# connector2.net
KiCad netlist of a schematic drawn in EAGLE
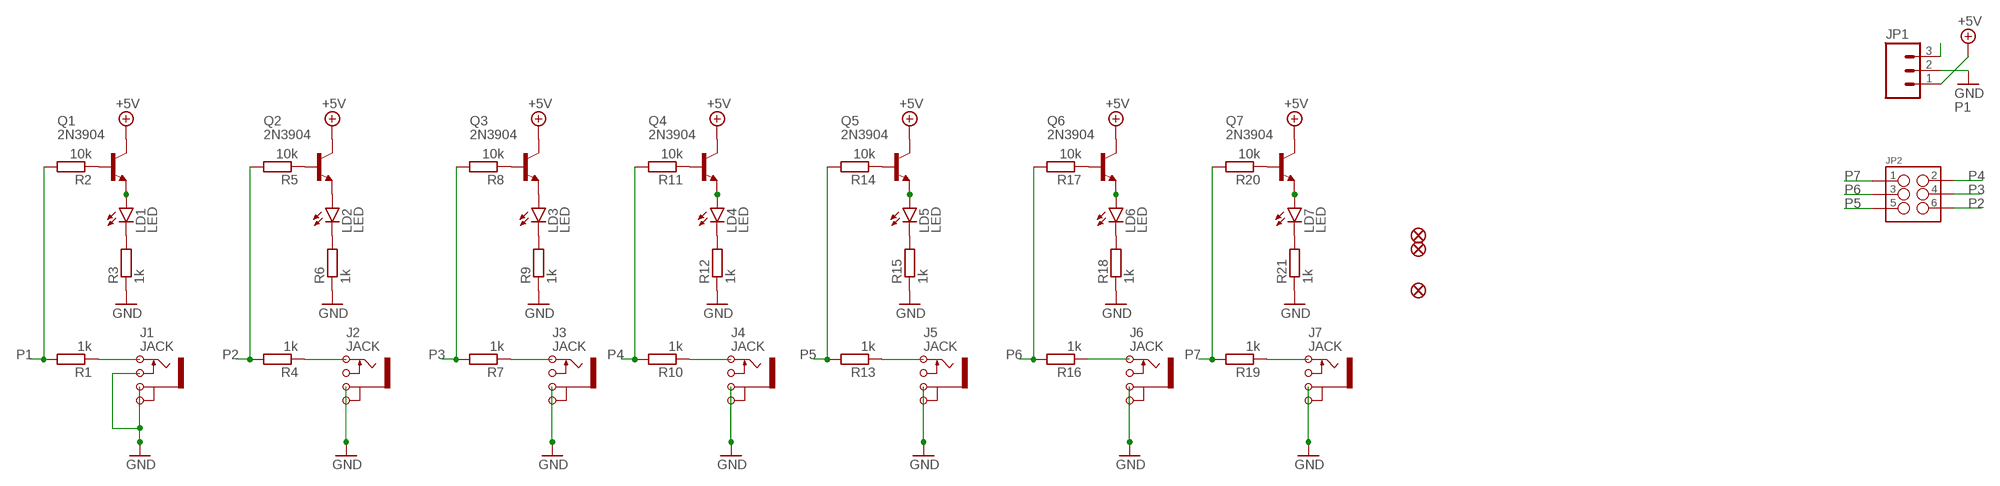
[diagram p0: schematic, sheet 1]

(export (version "E")
  (design (tool "Eeschema 10.0.6"))
  (components
    (comp (ref "FID1")
      (value "FIDUCIAL")
      (footprint "eagle-import:FIDUCIAL")
      (libsource (lib "eagle-import") (part "FIDUCIAL"))
    )
    (comp (ref "FID2")
      (value "FIDUCIAL")
      (footprint "eagle-import:FIDUCIAL")
      (libsource (lib "eagle-import") (part "FIDUCIAL"))
    )
    (comp (ref "FID3")
      (value "FIDUCIAL")
      (footprint "eagle-import:FIDUCIAL")
      (libsource (lib "eagle-import") (part "FIDUCIAL"))
    )
    (comp (ref "J1")
      (value "JACK")
      (footprint "eagle-import:JACK_MONO")
      (libsource (lib "eagle-import") (part "JACK_MONOJACK_MONO"))
    )
    (comp (ref "J2")
      (value "JACK")
      (footprint "eagle-import:JACK_MONO")
      (libsource (lib "eagle-import") (part "JACK_MONOJACK_MONO"))
    )
    (comp (ref "J3")
      (value "JACK")
      (footprint "eagle-import:JACK_MONO")
      (libsource (lib "eagle-import") (part "JACK_MONOJACK_MONO"))
    )
    (comp (ref "J4")
      (value "JACK")
      (footprint "eagle-import:JACK_MONO")
      (libsource (lib "eagle-import") (part "JACK_MONOJACK_MONO"))
    )
    (comp (ref "J5")
      (value "JACK")
      (footprint "eagle-import:JACK_MONO")
      (libsource (lib "eagle-import") (part "JACK_MONOJACK_MONO"))
    )
    (comp (ref "J6")
      (value "JACK")
      (footprint "eagle-import:JACK_MONO")
      (libsource (lib "eagle-import") (part "JACK_MONOJACK_MONO"))
    )
    (comp (ref "J7")
      (value "JACK")
      (footprint "eagle-import:JACK_MONO")
      (libsource (lib "eagle-import") (part "JACK_MONOJACK_MONO"))
    )
    (comp (ref "JP1")
      (value "M03LOCK")
      (footprint "eagle-import:1X03_LOCK")
      (libsource (lib "eagle-import") (part "M03LOCK"))
    )
    (comp (ref "JP2")
      (value "M03X2NO_SILK")
      (footprint "eagle-import:2X3-NS")
      (libsource (lib "eagle-import") (part "M03X2NO_SILK"))
    )
    (comp (ref "LD1")
      (value "LED")
      (footprint "eagle-import:LEDSMALLHOLES")
      (libsource (lib "eagle-import") (part "LED_THT"))
    )
    (comp (ref "LD2")
      (value "LED")
      (footprint "eagle-import:LEDSMALLHOLES")
      (libsource (lib "eagle-import") (part "LED_THT"))
    )
    (comp (ref "LD3")
      (value "LED")
      (footprint "eagle-import:LEDSMALLHOLES")
      (libsource (lib "eagle-import") (part "LED_THT"))
    )
    (comp (ref "LD4")
      (value "LED")
      (footprint "eagle-import:LEDSMALLHOLES")
      (libsource (lib "eagle-import") (part "LED_THT"))
    )
    (comp (ref "LD5")
      (value "LED")
      (footprint "eagle-import:LEDSMALLHOLES")
      (libsource (lib "eagle-import") (part "LED_THT"))
    )
    (comp (ref "LD6")
      (value "LED")
      (footprint "eagle-import:LEDSMALLHOLES")
      (libsource (lib "eagle-import") (part "LED_THT"))
    )
    (comp (ref "LD7")
      (value "LED")
      (footprint "eagle-import:LEDSMALLHOLES")
      (libsource (lib "eagle-import") (part "LED_THT"))
    )
    (comp (ref "Q1")
      (value "2N3904")
      (footprint "eagle-import:SOT23")
      (fields (field (name "MPN") "MMBT3904LT1G"))
      (libsource (lib "eagle-import") (part "2N3904"))
    )
    (comp (ref "Q2")
      (value "2N3904")
      (footprint "eagle-import:SOT23")
      (fields (field (name "MPN") "MMBT3904LT1G"))
      (libsource (lib "eagle-import") (part "2N3904"))
    )
    (comp (ref "Q3")
      (value "2N3904")
      (footprint "eagle-import:SOT23")
      (fields (field (name "MPN") "MMBT3904LT1G"))
      (libsource (lib "eagle-import") (part "2N3904"))
    )
    (comp (ref "Q4")
      (value "2N3904")
      (footprint "eagle-import:SOT23")
      (fields (field (name "MPN") "MMBT3904LT1G"))
      (libsource (lib "eagle-import") (part "2N3904"))
    )
    (comp (ref "Q5")
      (value "2N3904")
      (footprint "eagle-import:SOT23")
      (fields (field (name "MPN") "MMBT3904LT1G"))
      (libsource (lib "eagle-import") (part "2N3904"))
    )
    (comp (ref "Q6")
      (value "2N3904")
      (footprint "eagle-import:SOT23")
      (fields (field (name "MPN") "MMBT3904LT1G"))
      (libsource (lib "eagle-import") (part "2N3904"))
    )
    (comp (ref "Q7")
      (value "2N3904")
      (footprint "eagle-import:SOT23")
      (fields (field (name "MPN") "MMBT3904LT1G"))
      (libsource (lib "eagle-import") (part "2N3904"))
    )
    (comp (ref "R1")
      (value "1k")
      (footprint "eagle-import:RESISTOR0603")
      (libsource (lib "eagle-import") (part "RESISTOR0603"))
    )
    (comp (ref "R2")
      (value "10k")
      (footprint "eagle-import:RESISTOR0603")
      (libsource (lib "eagle-import") (part "RESISTOR0603"))
    )
    (comp (ref "R3")
      (value "1k")
      (footprint "eagle-import:RESISTOR0603")
      (libsource (lib "eagle-import") (part "RESISTOR0603"))
    )
    (comp (ref "R4")
      (value "1k")
      (footprint "eagle-import:RESISTOR0603")
      (libsource (lib "eagle-import") (part "RESISTOR0603"))
    )
    (comp (ref "R5")
      (value "10k")
      (footprint "eagle-import:RESISTOR0603")
      (libsource (lib "eagle-import") (part "RESISTOR0603"))
    )
    (comp (ref "R6")
      (value "1k")
      (footprint "eagle-import:RESISTOR0603")
      (libsource (lib "eagle-import") (part "RESISTOR0603"))
    )
    (comp (ref "R7")
      (value "1k")
      (footprint "eagle-import:RESISTOR0603")
      (libsource (lib "eagle-import") (part "RESISTOR0603"))
    )
    (comp (ref "R8")
      (value "10k")
      (footprint "eagle-import:RESISTOR0603")
      (libsource (lib "eagle-import") (part "RESISTOR0603"))
    )
    (comp (ref "R9")
      (value "1k")
      (footprint "eagle-import:RESISTOR0603")
      (libsource (lib "eagle-import") (part "RESISTOR0603"))
    )
    (comp (ref "R10")
      (value "1k")
      (footprint "eagle-import:RESISTOR0603")
      (libsource (lib "eagle-import") (part "RESISTOR0603"))
    )
    (comp (ref "R11")
      (value "10k")
      (footprint "eagle-import:RESISTOR0603")
      (libsource (lib "eagle-import") (part "RESISTOR0603"))
    )
    (comp (ref "R12")
      (value "1k")
      (footprint "eagle-import:RESISTOR0603")
      (libsource (lib "eagle-import") (part "RESISTOR0603"))
    )
    (comp (ref "R13")
      (value "1k")
      (footprint "eagle-import:RESISTOR0603")
      (libsource (lib "eagle-import") (part "RESISTOR0603"))
    )
    (comp (ref "R14")
      (value "10k")
      (footprint "eagle-import:RESISTOR0603")
      (libsource (lib "eagle-import") (part "RESISTOR0603"))
    )
    (comp (ref "R15")
      (value "1k")
      (footprint "eagle-import:RESISTOR0603")
      (libsource (lib "eagle-import") (part "RESISTOR0603"))
    )
    (comp (ref "R16")
      (value "1k")
      (footprint "eagle-import:RESISTOR0603")
      (libsource (lib "eagle-import") (part "RESISTOR0603"))
    )
    (comp (ref "R17")
      (value "10k")
      (footprint "eagle-import:RESISTOR0603")
      (libsource (lib "eagle-import") (part "RESISTOR0603"))
    )
    (comp (ref "R18")
      (value "1k")
      (footprint "eagle-import:RESISTOR0603")
      (libsource (lib "eagle-import") (part "RESISTOR0603"))
    )
    (comp (ref "R19")
      (value "1k")
      (footprint "eagle-import:RESISTOR0603")
      (libsource (lib "eagle-import") (part "RESISTOR0603"))
    )
    (comp (ref "R20")
      (value "10k")
      (footprint "eagle-import:RESISTOR0603")
      (libsource (lib "eagle-import") (part "RESISTOR0603"))
    )
    (comp (ref "R21")
      (value "1k")
      (footprint "eagle-import:RESISTOR0603")
      (libsource (lib "eagle-import") (part "RESISTOR0603"))
    )
  )
  (nets
    (net (code "1") (name "+5V") (class "Default")
      (node (ref "JP1") (pin "1") (pinfunction "1_1") (pintype "passive"))
      (node (ref "Q1") (pin "C") (pinfunction "C_C") (pintype "passive"))
      (node (ref "Q2") (pin "C") (pinfunction "C_C") (pintype "passive"))
      (node (ref "Q3") (pin "C") (pinfunction "C_C") (pintype "passive"))
      (node (ref "Q4") (pin "C") (pinfunction "C_C") (pintype "passive"))
      (node (ref "Q5") (pin "C") (pinfunction "C_C") (pintype "passive"))
      (node (ref "Q6") (pin "C") (pinfunction "C_C") (pintype "passive"))
      (node (ref "Q7") (pin "C") (pinfunction "C_C") (pintype "passive"))
    )
    (net (code "2") (name "/P1") (class "Default")
      (node (ref "JP1") (pin "3") (pinfunction "3_3") (pintype "passive"))
      (node (ref "R1") (pin "2") (pinfunction "2_2") (pintype "passive"))
      (node (ref "R2") (pin "2") (pinfunction "2_2") (pintype "passive"))
    )
    (net (code "3") (name "/P2") (class "Default")
      (node (ref "JP2") (pin "6") (pinfunction "6_6") (pintype "bidirectional"))
      (node (ref "R4") (pin "2") (pinfunction "2_2") (pintype "passive"))
      (node (ref "R5") (pin "2") (pinfunction "2_2") (pintype "passive"))
    )
    (net (code "4") (name "/P3") (class "Default")
      (node (ref "JP2") (pin "4") (pinfunction "4_4") (pintype "bidirectional"))
      (node (ref "R7") (pin "2") (pinfunction "2_2") (pintype "passive"))
      (node (ref "R8") (pin "2") (pinfunction "2_2") (pintype "passive"))
    )
    (net (code "5") (name "/P4") (class "Default")
      (node (ref "JP2") (pin "2") (pinfunction "2_2") (pintype "bidirectional"))
      (node (ref "R10") (pin "2") (pinfunction "2_2") (pintype "passive"))
      (node (ref "R11") (pin "2") (pinfunction "2_2") (pintype "passive"))
    )
    (net (code "6") (name "/P5") (class "Default")
      (node (ref "JP2") (pin "5") (pinfunction "5_5") (pintype "bidirectional"))
      (node (ref "R13") (pin "2") (pinfunction "2_2") (pintype "passive"))
      (node (ref "R14") (pin "2") (pinfunction "2_2") (pintype "passive"))
    )
    (net (code "7") (name "/P6") (class "Default")
      (node (ref "JP2") (pin "3") (pinfunction "3_3") (pintype "bidirectional"))
      (node (ref "R16") (pin "2") (pinfunction "2_2") (pintype "passive"))
      (node (ref "R17") (pin "2") (pinfunction "2_2") (pintype "passive"))
    )
    (net (code "8") (name "/P7") (class "Default")
      (node (ref "JP2") (pin "1") (pinfunction "1_1") (pintype "bidirectional"))
      (node (ref "R19") (pin "2") (pinfunction "2_2") (pintype "passive"))
      (node (ref "R20") (pin "2") (pinfunction "2_2") (pintype "passive"))
    )
    (net (code "9") (name "GND") (class "Default")
      (node (ref "J1") (pin "G1") (pinfunction "G1_G1") (pintype "passive"))
      (node (ref "J1") (pin "G2") (pinfunction "G2_G2") (pintype "passive"))
      (node (ref "J1") (pin "SW") (pinfunction "SW_SW") (pintype "passive"))
      (node (ref "J2") (pin "G1") (pinfunction "G1_G1") (pintype "passive"))
      (node (ref "J2") (pin "G2") (pinfunction "G2_G2") (pintype "passive"))
      (node (ref "J3") (pin "G1") (pinfunction "G1_G1") (pintype "passive"))
      (node (ref "J3") (pin "G2") (pinfunction "G2_G2") (pintype "passive"))
      (node (ref "J4") (pin "G1") (pinfunction "G1_G1") (pintype "passive"))
      (node (ref "J4") (pin "G2") (pinfunction "G2_G2") (pintype "passive"))
      (node (ref "J5") (pin "G1") (pinfunction "G1_G1") (pintype "passive"))
      (node (ref "J5") (pin "G2") (pinfunction "G2_G2") (pintype "passive"))
      (node (ref "J6") (pin "G1") (pinfunction "G1_G1") (pintype "passive"))
      (node (ref "J6") (pin "G2") (pinfunction "G2_G2") (pintype "passive"))
      (node (ref "J7") (pin "G1") (pinfunction "G1_G1") (pintype "passive"))
      (node (ref "J7") (pin "G2") (pinfunction "G2_G2") (pintype "passive"))
      (node (ref "JP1") (pin "2") (pinfunction "2_2") (pintype "passive"))
      (node (ref "R12") (pin "1") (pinfunction "1_1") (pintype "passive"))
      (node (ref "R15") (pin "1") (pinfunction "1_1") (pintype "passive"))
      (node (ref "R18") (pin "1") (pinfunction "1_1") (pintype "passive"))
      (node (ref "R21") (pin "1") (pinfunction "1_1") (pintype "passive"))
      (node (ref "R3") (pin "1") (pinfunction "1_1") (pintype "passive"))
      (node (ref "R6") (pin "1") (pinfunction "1_1") (pintype "passive"))
      (node (ref "R9") (pin "1") (pinfunction "1_1") (pintype "passive"))
    )
    (net (code "10") (name "Net-(J1-PadT)") (class "Default")
      (node (ref "J1") (pin "T") (pinfunction "T_T") (pintype "passive"))
      (node (ref "R1") (pin "1") (pinfunction "1_1") (pintype "passive"))
    )
    (net (code "11") (name "Net-(J2-PadT)") (class "Default")
      (node (ref "J2") (pin "T") (pinfunction "T_T") (pintype "passive"))
      (node (ref "R4") (pin "1") (pinfunction "1_1") (pintype "passive"))
    )
    (net (code "12") (name "Net-(J3-PadT)") (class "Default")
      (node (ref "J3") (pin "T") (pinfunction "T_T") (pintype "passive"))
      (node (ref "R7") (pin "1") (pinfunction "1_1") (pintype "passive"))
    )
    (net (code "13") (name "Net-(J4-PadT)") (class "Default")
      (node (ref "J4") (pin "T") (pinfunction "T_T") (pintype "passive"))
      (node (ref "R10") (pin "1") (pinfunction "1_1") (pintype "passive"))
    )
    (net (code "14") (name "Net-(J5-PadT)") (class "Default")
      (node (ref "J5") (pin "T") (pinfunction "T_T") (pintype "passive"))
      (node (ref "R13") (pin "1") (pinfunction "1_1") (pintype "passive"))
    )
    (net (code "15") (name "Net-(J6-PadT)") (class "Default")
      (node (ref "J6") (pin "T") (pinfunction "T_T") (pintype "passive"))
      (node (ref "R16") (pin "1") (pinfunction "1_1") (pintype "passive"))
    )
    (net (code "16") (name "Net-(J7-PadT)") (class "Default")
      (node (ref "J7") (pin "T") (pinfunction "T_T") (pintype "passive"))
      (node (ref "R19") (pin "1") (pinfunction "1_1") (pintype "passive"))
    )
    (net (code "17") (name "Net-(LD1-C)") (class "Default")
      (node (ref "LD1") (pin "K") (pinfunction "C_K") (pintype "passive"))
      (node (ref "R3") (pin "2") (pinfunction "2_2") (pintype "passive"))
    )
    (net (code "18") (name "Net-(LD1-PadA)") (class "Default")
      (node (ref "LD1") (pin "A") (pinfunction "A_A") (pintype "passive"))
      (node (ref "Q1") (pin "E") (pinfunction "E_E") (pintype "passive"))
    )
    (net (code "19") (name "Net-(LD2-C)") (class "Default")
      (node (ref "LD2") (pin "K") (pinfunction "C_K") (pintype "passive"))
      (node (ref "R6") (pin "2") (pinfunction "2_2") (pintype "passive"))
    )
    (net (code "20") (name "Net-(LD2-PadA)") (class "Default")
      (node (ref "LD2") (pin "A") (pinfunction "A_A") (pintype "passive"))
      (node (ref "Q2") (pin "E") (pinfunction "E_E") (pintype "passive"))
    )
    (net (code "21") (name "Net-(LD3-C)") (class "Default")
      (node (ref "LD3") (pin "K") (pinfunction "C_K") (pintype "passive"))
      (node (ref "R9") (pin "2") (pinfunction "2_2") (pintype "passive"))
    )
    (net (code "22") (name "Net-(LD3-PadA)") (class "Default")
      (node (ref "LD3") (pin "A") (pinfunction "A_A") (pintype "passive"))
      (node (ref "Q3") (pin "E") (pinfunction "E_E") (pintype "passive"))
    )
    (net (code "23") (name "Net-(LD4-C)") (class "Default")
      (node (ref "LD4") (pin "K") (pinfunction "C_K") (pintype "passive"))
      (node (ref "R12") (pin "2") (pinfunction "2_2") (pintype "passive"))
    )
    (net (code "24") (name "Net-(LD4-PadA)") (class "Default")
      (node (ref "LD4") (pin "A") (pinfunction "A_A") (pintype "passive"))
      (node (ref "Q4") (pin "E") (pinfunction "E_E") (pintype "passive"))
    )
    (net (code "25") (name "Net-(LD5-C)") (class "Default")
      (node (ref "LD5") (pin "K") (pinfunction "C_K") (pintype "passive"))
      (node (ref "R15") (pin "2") (pinfunction "2_2") (pintype "passive"))
    )
    (net (code "26") (name "Net-(LD5-PadA)") (class "Default")
      (node (ref "LD5") (pin "A") (pinfunction "A_A") (pintype "passive"))
      (node (ref "Q5") (pin "E") (pinfunction "E_E") (pintype "passive"))
    )
    (net (code "27") (name "Net-(LD6-C)") (class "Default")
      (node (ref "LD6") (pin "K") (pinfunction "C_K") (pintype "passive"))
      (node (ref "R18") (pin "2") (pinfunction "2_2") (pintype "passive"))
    )
    (net (code "28") (name "Net-(LD6-PadA)") (class "Default")
      (node (ref "LD6") (pin "A") (pinfunction "A_A") (pintype "passive"))
      (node (ref "Q6") (pin "E") (pinfunction "E_E") (pintype "passive"))
    )
    (net (code "29") (name "Net-(LD7-C)") (class "Default")
      (node (ref "LD7") (pin "K") (pinfunction "C_K") (pintype "passive"))
      (node (ref "R21") (pin "2") (pinfunction "2_2") (pintype "passive"))
    )
    (net (code "30") (name "Net-(LD7-PadA)") (class "Default")
      (node (ref "LD7") (pin "A") (pinfunction "A_A") (pintype "passive"))
      (node (ref "Q7") (pin "E") (pinfunction "E_E") (pintype "passive"))
    )
    (net (code "31") (name "Net-(Q1-PadB)") (class "Default")
      (node (ref "Q1") (pin "B") (pinfunction "B_B") (pintype "passive"))
      (node (ref "R2") (pin "1") (pinfunction "1_1") (pintype "passive"))
    )
    (net (code "32") (name "Net-(Q2-PadB)") (class "Default")
      (node (ref "Q2") (pin "B") (pinfunction "B_B") (pintype "passive"))
      (node (ref "R5") (pin "1") (pinfunction "1_1") (pintype "passive"))
    )
    (net (code "33") (name "Net-(Q3-PadB)") (class "Default")
      (node (ref "Q3") (pin "B") (pinfunction "B_B") (pintype "passive"))
      (node (ref "R8") (pin "1") (pinfunction "1_1") (pintype "passive"))
    )
    (net (code "34") (name "Net-(Q4-PadB)") (class "Default")
      (node (ref "Q4") (pin "B") (pinfunction "B_B") (pintype "passive"))
      (node (ref "R11") (pin "1") (pinfunction "1_1") (pintype "passive"))
    )
    (net (code "35") (name "Net-(Q5-PadB)") (class "Default")
      (node (ref "Q5") (pin "B") (pinfunction "B_B") (pintype "passive"))
      (node (ref "R14") (pin "1") (pinfunction "1_1") (pintype "passive"))
    )
    (net (code "36") (name "Net-(Q6-PadB)") (class "Default")
      (node (ref "Q6") (pin "B") (pinfunction "B_B") (pintype "passive"))
      (node (ref "R17") (pin "1") (pinfunction "1_1") (pintype "passive"))
    )
    (net (code "37") (name "Net-(Q7-PadB)") (class "Default")
      (node (ref "Q7") (pin "B") (pinfunction "B_B") (pintype "passive"))
      (node (ref "R20") (pin "1") (pinfunction "1_1") (pintype "passive"))
    )
    (net (code "38") (name "unconnected-(J2-PadSW)") (class "Default")
      (node (ref "J2") (pin "SW") (pinfunction "SW_SW") (pintype "passive"))
    )
    (net (code "39") (name "unconnected-(J3-PadSW)") (class "Default")
      (node (ref "J3") (pin "SW") (pinfunction "SW_SW") (pintype "passive"))
    )
    (net (code "40") (name "unconnected-(J4-PadSW)") (class "Default")
      (node (ref "J4") (pin "SW") (pinfunction "SW_SW") (pintype "passive"))
    )
    (net (code "41") (name "unconnected-(J5-PadSW)") (class "Default")
      (node (ref "J5") (pin "SW") (pinfunction "SW_SW") (pintype "passive"))
    )
    (net (code "42") (name "unconnected-(J6-PadSW)") (class "Default")
      (node (ref "J6") (pin "SW") (pinfunction "SW_SW") (pintype "passive"))
    )
    (net (code "43") (name "unconnected-(J7-PadSW)") (class "Default")
      (node (ref "J7") (pin "SW") (pinfunction "SW_SW") (pintype "passive"))
    )
  )
)
